# ProProject_Access_Control_USB_Adapter_20.net
KiCad netlist of a schematic drawn in EasyEDA Pro
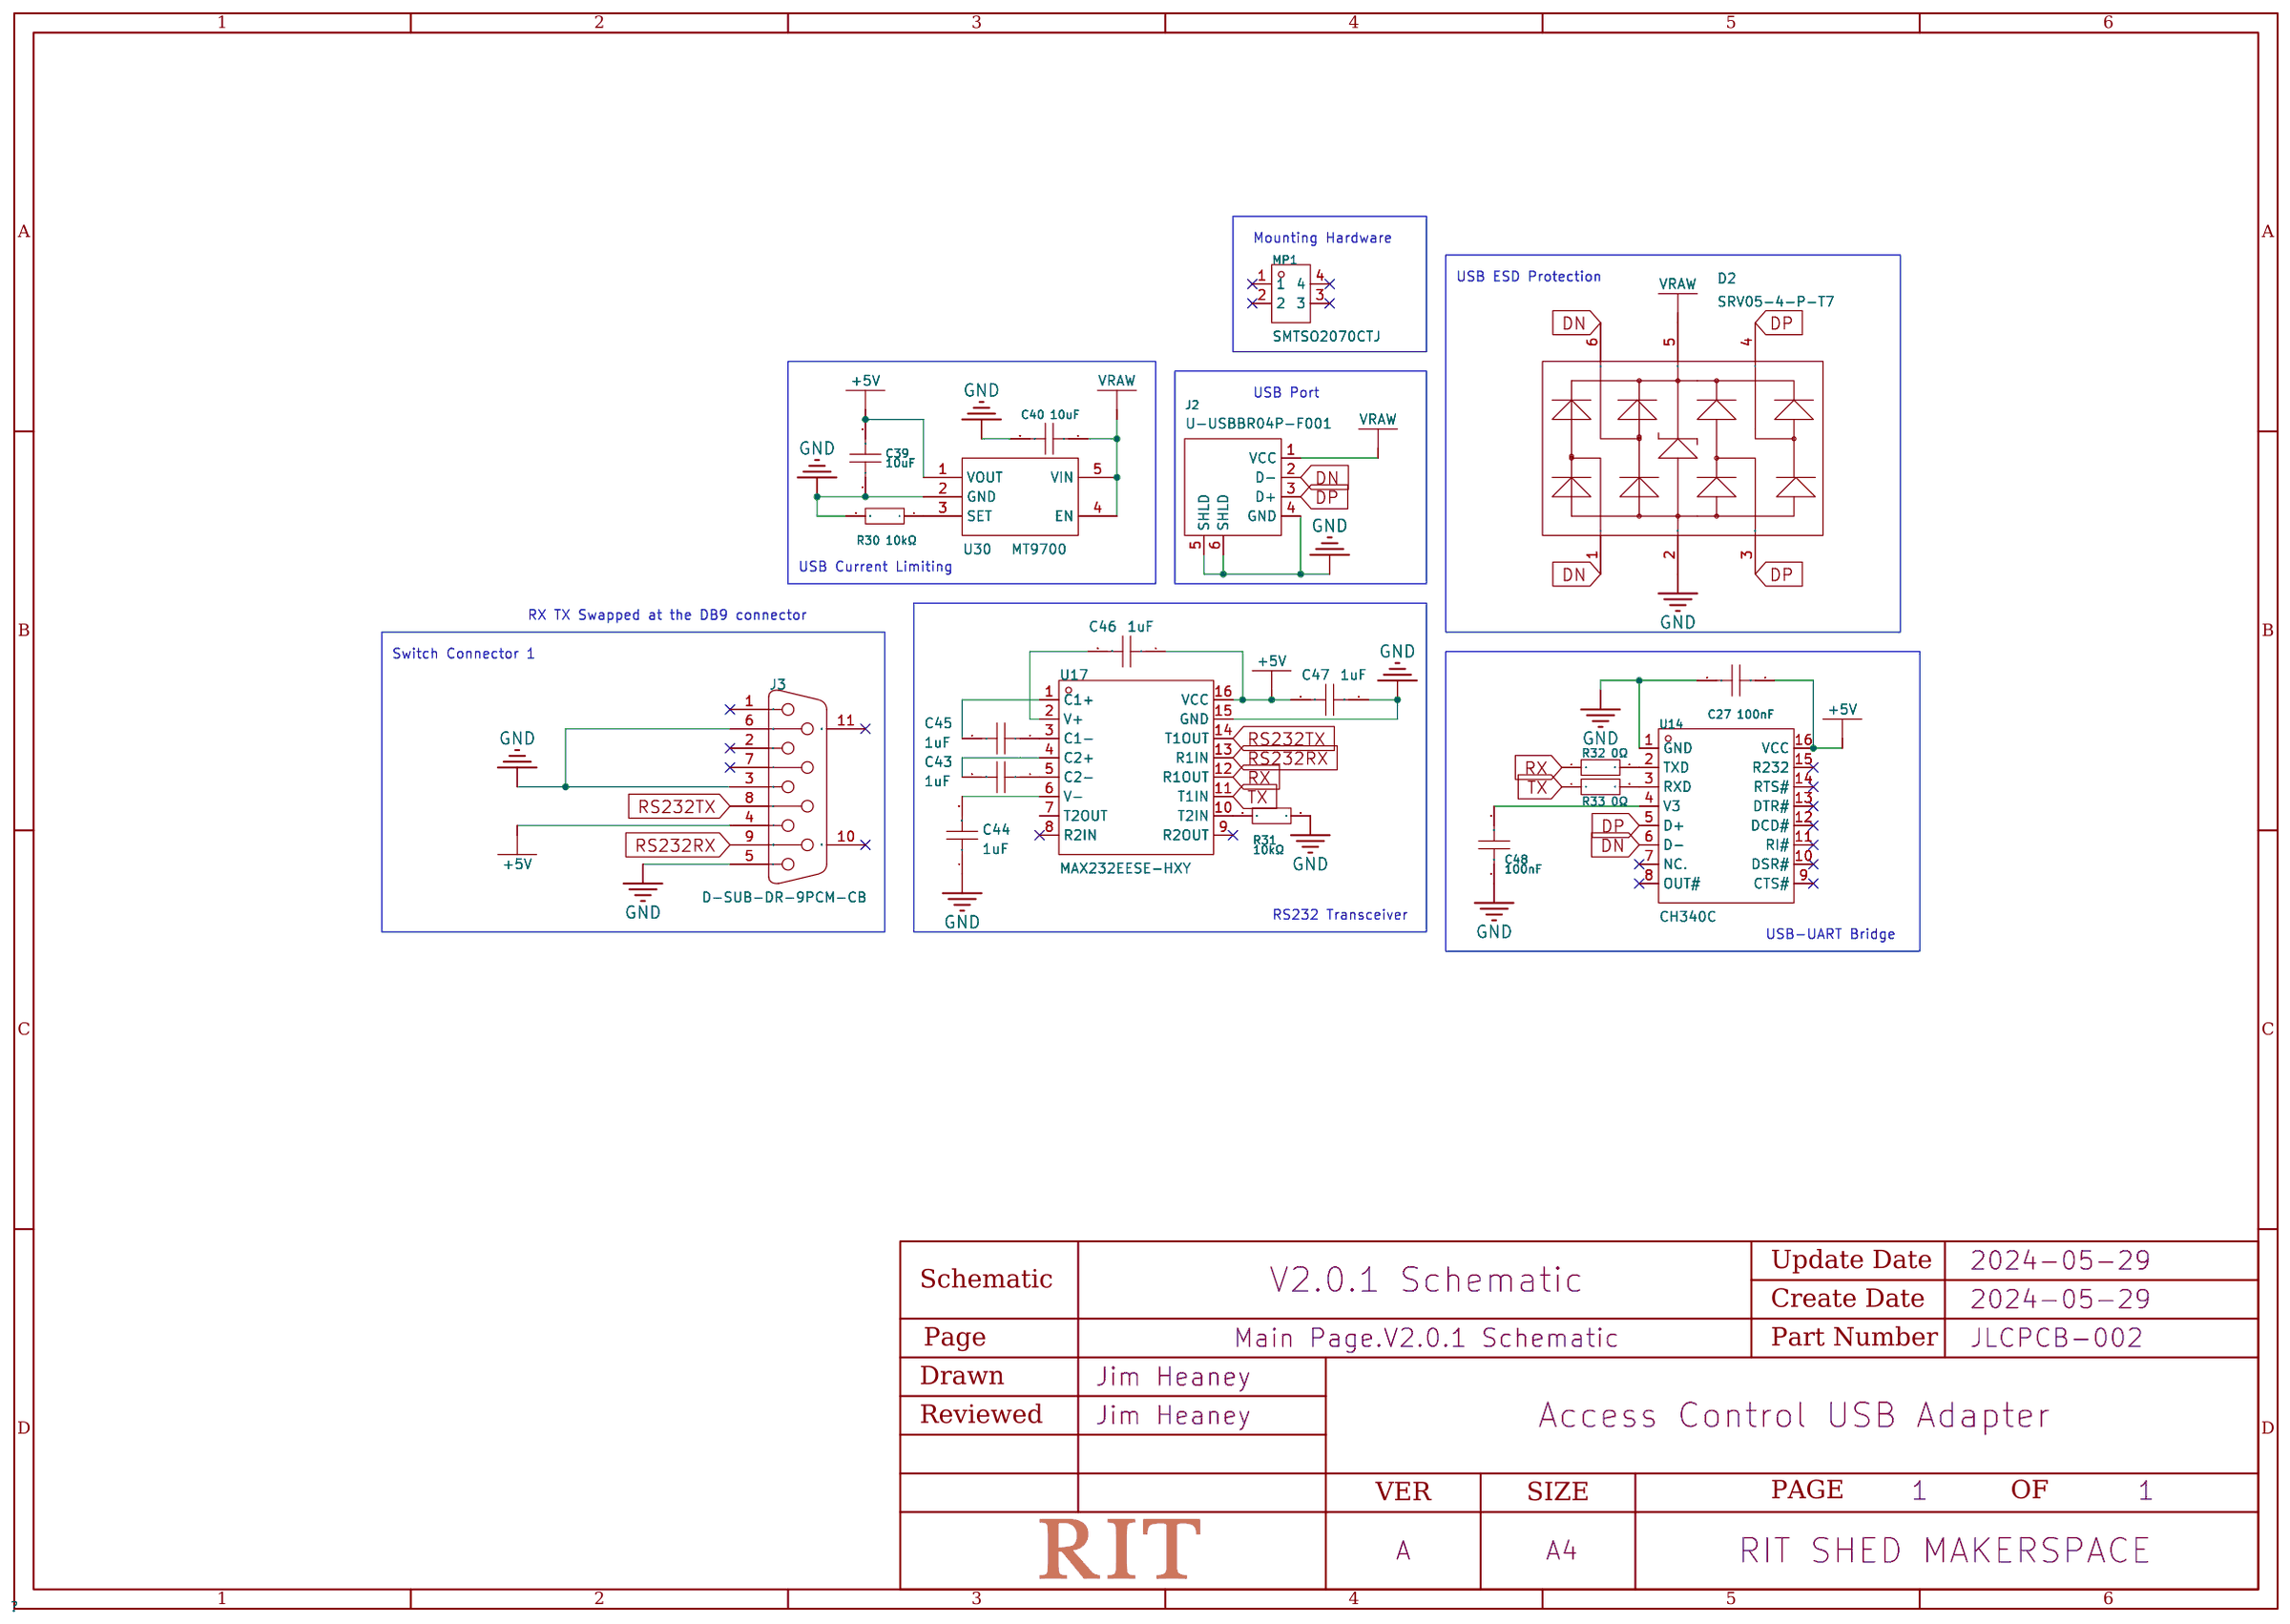
[diagram p0: schematic sheet]

(export (version "E")
  (design (tool "Eeschema 10.0.6"))
  (components
    (comp (ref "C27")
      (value "100nF")
      (footprint "easyedapro:C0603")
      (fields
        (field (name "Manufacturer Part") "CC0603KRX7R9BB104")
        (field (name "Manufacturer") "YAGEO(国巨)")
      )
      (libsource (lib "easyedapro") (part "CC0603KRX7R9BB104"))
    )
    (comp (ref "C39")
      (value "10uF")
      (footprint "easyedapro:C0603")
      (fields
        (field (name "Manufacturer Part") "CL10A106MA8NRNC")
        (field (name "Manufacturer") "SAMSUNG(三星)")
      )
      (libsource (lib "easyedapro") (part "CL10A106MA8NRNC"))
    )
    (comp (ref "C40")
      (value "10uF")
      (footprint "easyedapro:C0603")
      (fields
        (field (name "Manufacturer Part") "CL10A106MA8NRNC")
        (field (name "Manufacturer") "SAMSUNG(三星)")
      )
      (libsource (lib "easyedapro") (part "CL10A106MA8NRNC"))
    )
    (comp (ref "C43")
      (value "1uF")
      (footprint "easyedapro:C0603")
      (fields
        (field (name "Manufacturer Part") "CL10A105KB8NNNC")
        (field (name "Manufacturer") "SAMSUNG(三星)")
      )
      (libsource (lib "easyedapro") (part "CL10A105KB8NNNC"))
    )
    (comp (ref "C44")
      (value "1uF")
      (footprint "easyedapro:C0603")
      (fields
        (field (name "Manufacturer Part") "CL10A105KB8NNNC")
        (field (name "Manufacturer") "SAMSUNG(三星)")
      )
      (libsource (lib "easyedapro") (part "CL10A105KB8NNNC"))
    )
    (comp (ref "C45")
      (value "1uF")
      (footprint "easyedapro:C0603")
      (fields
        (field (name "Manufacturer Part") "CL10A105KB8NNNC")
        (field (name "Manufacturer") "SAMSUNG(三星)")
      )
      (libsource (lib "easyedapro") (part "CL10A105KB8NNNC"))
    )
    (comp (ref "C46")
      (value "1uF")
      (footprint "easyedapro:C0603")
      (fields
        (field (name "Manufacturer Part") "CL10A105KB8NNNC")
        (field (name "Manufacturer") "SAMSUNG(三星)")
      )
      (libsource (lib "easyedapro") (part "CL10A105KB8NNNC"))
    )
    (comp (ref "C47")
      (value "1uF")
      (footprint "easyedapro:C0603")
      (fields
        (field (name "Manufacturer Part") "CL10A105KB8NNNC")
        (field (name "Manufacturer") "SAMSUNG(三星)")
      )
      (libsource (lib "easyedapro") (part "CL10A105KB8NNNC"))
    )
    (comp (ref "C48")
      (value "100nF")
      (footprint "easyedapro:C0603")
      (fields
        (field (name "Manufacturer Part") "CC0603KRX7R9BB104")
        (field (name "Manufacturer") "YAGEO(国巨)")
      )
      (libsource (lib "easyedapro") (part "CC0603KRX7R9BB104"))
    )
    (comp (ref "D2")
      (value "SRV05-4-P-T7")
      (footprint "easyedapro:SOT-23-6_L2.9-W1.6-P0.95-LS2.8-BR")
      (fields (field (name "Manufacturer") "PROTEK"))
      (libsource (lib "easyedapro") (part "SRV05-4-P-T7"))
    )
    (comp (ref "J2")
      (value "U-USBBR04P-F001")
      (footprint "easyedapro:USB-B-TH_U241-041N-1BR85-1")
      (fields (field (name "Manufacturer") "Ckmtw(灿科盟)"))
      (libsource (lib "easyedapro") (part "U-USBBR04P-F001"))
    )
    (comp (ref "J3")
      (value "D-SUB-DR-9PCM-CB")
      (footprint "easyedapro:DB9-TH_ID09S33E4GV00LF")
      (fields (field (name "Manufacturer") "XUNPU(讯普)"))
      (libsource (lib "easyedapro") (part "D-SUB-DR-9PCM-CB"))
    )
    (comp (ref "MP1")
      (value "SMTSO2070CTJ")
      (footprint "easyedapro:SMD_BD5.6-L5.6-W5.6-D3.6")
      (fields (field (name "Manufacturer") "Sinhoo(雄和远景)"))
      (libsource (lib "easyedapro") (part "SMTSO2070CTJ"))
    )
    (comp (ref "R30")
      (value "10kΩ")
      (footprint "easyedapro:R0603")
      (fields
        (field (name "Manufacturer Part") "0603WAF1002T5E")
        (field (name "Manufacturer") "UNI-ROYAL(厚声)")
      )
      (libsource (lib "easyedapro") (part "0603WAF1002T5E"))
    )
    (comp (ref "R31")
      (value "10kΩ")
      (footprint "easyedapro:R0603")
      (fields
        (field (name "Manufacturer Part") "0603WAF1002T5E")
        (field (name "Manufacturer") "UNI-ROYAL(厚声)")
      )
      (libsource (lib "easyedapro") (part "0603WAF1002T5E"))
    )
    (comp (ref "R32")
      (value "0Ω")
      (footprint "easyedapro:R1206")
      (fields
        (field (name "Manufacturer Part") "1206W4F0000T5E")
        (field (name "Manufacturer") "UNI-ROYAL(厚声)")
      )
      (libsource (lib "easyedapro") (part "1206W4F0000T5E"))
    )
    (comp (ref "R33")
      (value "0Ω")
      (footprint "easyedapro:R1206")
      (fields
        (field (name "Manufacturer Part") "1206W4F0000T5E")
        (field (name "Manufacturer") "UNI-ROYAL(厚声)")
      )
      (libsource (lib "easyedapro") (part "1206W4F0000T5E"))
    )
    (comp (ref "U14")
      (value "CH340C")
      (footprint "easyedapro:SOP-16_L10.0-W3.9-P1.27-LS6.0-BL")
      (fields (field (name "Manufacturer") "WCH(南京沁恒)"))
      (libsource (lib "easyedapro") (part "CH340C"))
    )
    (comp (ref "U17")
      (value "MAX232EESE-HXY")
      (footprint "easyedapro:SOP-16_L9.9-W3.9-P1.27-LS6.0-BL")
      (description "Driver/receiver:2/2 Data Rate:120Kbps Data Rate:120Kbps Supply Voltage:5V Supply Voltage:5V")
      (fields (field (name "Manufacturer") "HXY MOSFET(华轩阳电子)"))
      (libsource (lib "easyedapro") (part "MAX232EESE-HXY"))
    )
    (comp (ref "U30")
      (value "MT9700")
      (footprint "easyedapro:SOT-23-5_L3.0-W1.7-P0.95-LS2.8-BR")
      (fields (field (name "Manufacturer") "西安航天民芯"))
      (libsource (lib "easyedapro") (part "MT9700"))
    )
  )
  (nets
    (net (code "1") (name "+5V") (class "Default")
      (node (ref "C27") (pin "2") (pinfunction "2_2") (pintype "input"))
      (node (ref "C39") (pin "2") (pinfunction "2_2") (pintype "input"))
      (node (ref "C46") (pin "1") (pinfunction "1_1") (pintype "unspecified"))
      (node (ref "C47") (pin "2") (pinfunction "2_2") (pintype "unspecified"))
      (node (ref "J3") (pin "4") (pinfunction "4_4") (pintype "input"))
      (node (ref "U14") (pin "16") (pinfunction "VCC_16") (pintype "input"))
      (node (ref "U17") (pin "16") (pinfunction "VCC_16") (pintype "unspecified"))
      (node (ref "U30") (pin "1") (pinfunction "VOUT_1") (pintype "unspecified"))
    )
    (net (code "2") (name "DN") (class "Default")
      (node (ref "D2") (pin "1") (pinfunction "1_1") (pintype "input"))
      (node (ref "D2") (pin "6") (pinfunction "6_6") (pintype "input"))
      (node (ref "J2") (pin "2") (pinfunction "D-_2") (pintype "input"))
      (node (ref "U14") (pin "6") (pinfunction "D-_6") (pintype "input"))
    )
    (net (code "3") (name "DP") (class "Default")
      (node (ref "D2") (pin "3") (pinfunction "3_3") (pintype "input"))
      (node (ref "D2") (pin "4") (pinfunction "4_4") (pintype "input"))
      (node (ref "J2") (pin "3") (pinfunction "D+_3") (pintype "input"))
      (node (ref "U14") (pin "5") (pinfunction "D+_5") (pintype "input"))
    )
    (net (code "4") (name "GND") (class "Default")
      (node (ref "C27") (pin "1") (pinfunction "1_1") (pintype "input"))
      (node (ref "C39") (pin "1") (pinfunction "1_1") (pintype "input"))
      (node (ref "C40") (pin "2") (pinfunction "2_2") (pintype "input"))
      (node (ref "C44") (pin "1") (pinfunction "1_1") (pintype "unspecified"))
      (node (ref "C47") (pin "1") (pinfunction "1_1") (pintype "unspecified"))
      (node (ref "C48") (pin "1") (pinfunction "1_1") (pintype "input"))
      (node (ref "D2") (pin "2") (pinfunction "2_2") (pintype "input"))
      (node (ref "J2") (pin "4") (pinfunction "GND_4") (pintype "input"))
      (node (ref "J2") (pin "5") (pinfunction "SHLD_5") (pintype "input"))
      (node (ref "J2") (pin "6") (pinfunction "SHLD_6") (pintype "input"))
      (node (ref "J3") (pin "3") (pinfunction "3_3") (pintype "input"))
      (node (ref "J3") (pin "5") (pinfunction "5_5") (pintype "input"))
      (node (ref "J3") (pin "6") (pinfunction "6_6") (pintype "input"))
      (node (ref "R30") (pin "2") (pinfunction "2_2") (pintype "input"))
      (node (ref "R31") (pin "1") (pinfunction "1_1") (pintype "input"))
      (node (ref "U14") (pin "1") (pinfunction "GND_1") (pintype "input"))
      (node (ref "U17") (pin "15") (pinfunction "GND_15") (pintype "unspecified"))
      (node (ref "U30") (pin "2") (pinfunction "GND_2") (pintype "unspecified"))
    )
    (net (code "5") (name "Net-(U14-RXD)") (class "Default")
      (node (ref "R33") (pin "2") (pinfunction "2_2") (pintype "input"))
      (node (ref "U14") (pin "3") (pinfunction "RXD_3") (pintype "input"))
    )
    (net (code "6") (name "Net-(U14-TXD)") (class "Default")
      (node (ref "R32") (pin "2") (pinfunction "2_2") (pintype "input"))
      (node (ref "U14") (pin "2") (pinfunction "TXD_2") (pintype "input"))
    )
    (net (code "7") (name "Net-(U14-V3)") (class "Default")
      (node (ref "C48") (pin "2") (pinfunction "2_2") (pintype "input"))
      (node (ref "U14") (pin "4") (pinfunction "V3_4") (pintype "input"))
    )
    (net (code "8") (name "Net-(U17-C1+)") (class "Default")
      (node (ref "C45") (pin "2") (pinfunction "2_2") (pintype "unspecified"))
      (node (ref "U17") (pin "1") (pinfunction "C1+_1") (pintype "unspecified"))
    )
    (net (code "9") (name "Net-(U17-C1-)") (class "Default")
      (node (ref "C45") (pin "1") (pinfunction "1_1") (pintype "unspecified"))
      (node (ref "U17") (pin "3") (pinfunction "C1-_3") (pintype "unspecified"))
    )
    (net (code "10") (name "Net-(U17-C2+)") (class "Default")
      (node (ref "C43") (pin "2") (pinfunction "2_2") (pintype "unspecified"))
      (node (ref "U17") (pin "4") (pinfunction "C2+_4") (pintype "unspecified"))
    )
    (net (code "11") (name "Net-(U17-C2-)") (class "Default")
      (node (ref "C43") (pin "1") (pinfunction "1_1") (pintype "unspecified"))
      (node (ref "U17") (pin "5") (pinfunction "C2-_5") (pintype "unspecified"))
    )
    (net (code "12") (name "Net-(U17-T2IN)") (class "Default")
      (node (ref "R31") (pin "2") (pinfunction "2_2") (pintype "input"))
      (node (ref "U17") (pin "10") (pinfunction "T2IN_10") (pintype "unspecified"))
    )
    (net (code "13") (name "Net-(U17-V+)") (class "Default")
      (node (ref "C46") (pin "2") (pinfunction "2_2") (pintype "unspecified"))
      (node (ref "U17") (pin "2") (pinfunction "V+_2") (pintype "unspecified"))
    )
    (net (code "14") (name "Net-(U17-V-)") (class "Default")
      (node (ref "C44") (pin "2") (pinfunction "2_2") (pintype "unspecified"))
      (node (ref "U17") (pin "6") (pinfunction "V-_6") (pintype "unspecified"))
    )
    (net (code "15") (name "Net-(U30-SET)") (class "Default")
      (node (ref "R30") (pin "1") (pinfunction "1_1") (pintype "input"))
      (node (ref "U30") (pin "3") (pinfunction "SET_3") (pintype "unspecified"))
    )
    (net (code "16") (name "RS232RX") (class "Default")
      (node (ref "J3") (pin "9") (pinfunction "9_9") (pintype "input"))
      (node (ref "U17") (pin "13") (pinfunction "R1IN_13") (pintype "unspecified"))
    )
    (net (code "17") (name "RS232TX") (class "Default")
      (node (ref "J3") (pin "8") (pinfunction "8_8") (pintype "input"))
      (node (ref "U17") (pin "14") (pinfunction "T1OUT_14") (pintype "unspecified"))
    )
    (net (code "18") (name "RX") (class "Default")
      (node (ref "R32") (pin "1") (pinfunction "1_1") (pintype "input"))
      (node (ref "U17") (pin "12") (pinfunction "R1OUT_12") (pintype "unspecified"))
    )
    (net (code "19") (name "TX") (class "Default")
      (node (ref "R33") (pin "1") (pinfunction "1_1") (pintype "input"))
      (node (ref "U17") (pin "11") (pinfunction "T1IN_11") (pintype "unspecified"))
    )
    (net (code "20") (name "VRAW") (class "Default")
      (node (ref "C40") (pin "1") (pinfunction "1_1") (pintype "input"))
      (node (ref "D2") (pin "5") (pinfunction "5_5") (pintype "input"))
      (node (ref "J2") (pin "1") (pinfunction "VCC_1") (pintype "input"))
      (node (ref "U30") (pin "4") (pinfunction "EN_4") (pintype "unspecified"))
      (node (ref "U30") (pin "5") (pinfunction "VIN_5") (pintype "unspecified"))
    )
    (net (code "21") (name "unconnected-(J3-MH1-Pad10)") (class "Default")
      (node (ref "J3") (pin "10") (pinfunction "MH1_10") (pintype "input+no_connect"))
    )
    (net (code "22") (name "unconnected-(J3-MH2-Pad11)") (class "Default")
      (node (ref "J3") (pin "11") (pinfunction "MH2_11") (pintype "input+no_connect"))
    )
    (net (code "23") (name "unconnected-(J3-Pad1)") (class "Default")
      (node (ref "J3") (pin "1") (pinfunction "1_1") (pintype "input+no_connect"))
    )
    (net (code "24") (name "unconnected-(J3-Pad2)") (class "Default")
      (node (ref "J3") (pin "2") (pinfunction "2_2") (pintype "input+no_connect"))
    )
    (net (code "25") (name "unconnected-(J3-Pad7)") (class "Default")
      (node (ref "J3") (pin "7") (pinfunction "7_7") (pintype "input+no_connect"))
    )
    (net (code "26") (name "unconnected-(MP1-Pad1)") (class "Default")
      (node (ref "MP1") (pin "1") (pinfunction "1_1") (pintype "input+no_connect"))
    )
    (net (code "27") (name "unconnected-(MP1-Pad2)") (class "Default")
      (node (ref "MP1") (pin "2") (pinfunction "2_2") (pintype "input+no_connect"))
    )
    (net (code "28") (name "unconnected-(MP1-Pad3)") (class "Default")
      (node (ref "MP1") (pin "3") (pinfunction "3_3") (pintype "input+no_connect"))
    )
    (net (code "29") (name "unconnected-(MP1-Pad4)") (class "Default")
      (node (ref "MP1") (pin "4") (pinfunction "4_4") (pintype "input+no_connect"))
    )
    (net (code "30") (name "unconnected-(U14-CTS#-Pad9)") (class "Default")
      (node (ref "U14") (pin "9") (pinfunction "CTS#_9") (pintype "input+no_connect"))
    )
    (net (code "31") (name "unconnected-(U14-DCD#-Pad12)") (class "Default")
      (node (ref "U14") (pin "12") (pinfunction "DCD#_12") (pintype "input+no_connect"))
    )
    (net (code "32") (name "unconnected-(U14-DSR#-Pad10)") (class "Default")
      (node (ref "U14") (pin "10") (pinfunction "DSR#_10") (pintype "input+no_connect"))
    )
    (net (code "33") (name "unconnected-(U14-DTR#-Pad13)") (class "Default")
      (node (ref "U14") (pin "13") (pinfunction "DTR#_13") (pintype "input+no_connect"))
    )
    (net (code "34") (name "unconnected-(U14-NC.-Pad7)") (class "Default")
      (node (ref "U14") (pin "7") (pinfunction "NC._7") (pintype "input+no_connect"))
    )
    (net (code "35") (name "unconnected-(U14-OUT#-Pad8)") (class "Default")
      (node (ref "U14") (pin "8") (pinfunction "OUT#_8") (pintype "input+no_connect"))
    )
    (net (code "36") (name "unconnected-(U14-R232-Pad15)") (class "Default")
      (node (ref "U14") (pin "15") (pinfunction "R232_15") (pintype "input+no_connect"))
    )
    (net (code "37") (name "unconnected-(U14-RI#-Pad11)") (class "Default")
      (node (ref "U14") (pin "11") (pinfunction "RI#_11") (pintype "input+no_connect"))
    )
    (net (code "38") (name "unconnected-(U14-RTS#-Pad14)") (class "Default")
      (node (ref "U14") (pin "14") (pinfunction "RTS#_14") (pintype "input+no_connect"))
    )
    (net (code "39") (name "unconnected-(U17-R2IN-Pad8)") (class "Default")
      (node (ref "U17") (pin "8") (pinfunction "R2IN_8") (pintype "unspecified+no_connect"))
    )
    (net (code "40") (name "unconnected-(U17-R2OUT-Pad9)") (class "Default")
      (node (ref "U17") (pin "9") (pinfunction "R2OUT_9") (pintype "unspecified+no_connect"))
    )
    (net (code "41") (name "unconnected-(U17-T2OUT-Pad7)") (class "Default")
      (node (ref "U17") (pin "7") (pinfunction "T2OUT_7") (pintype "unspecified"))
    )
  )
)
